# Thermistors.net
KiCad netlist of a schematic drawn in Altium Designer
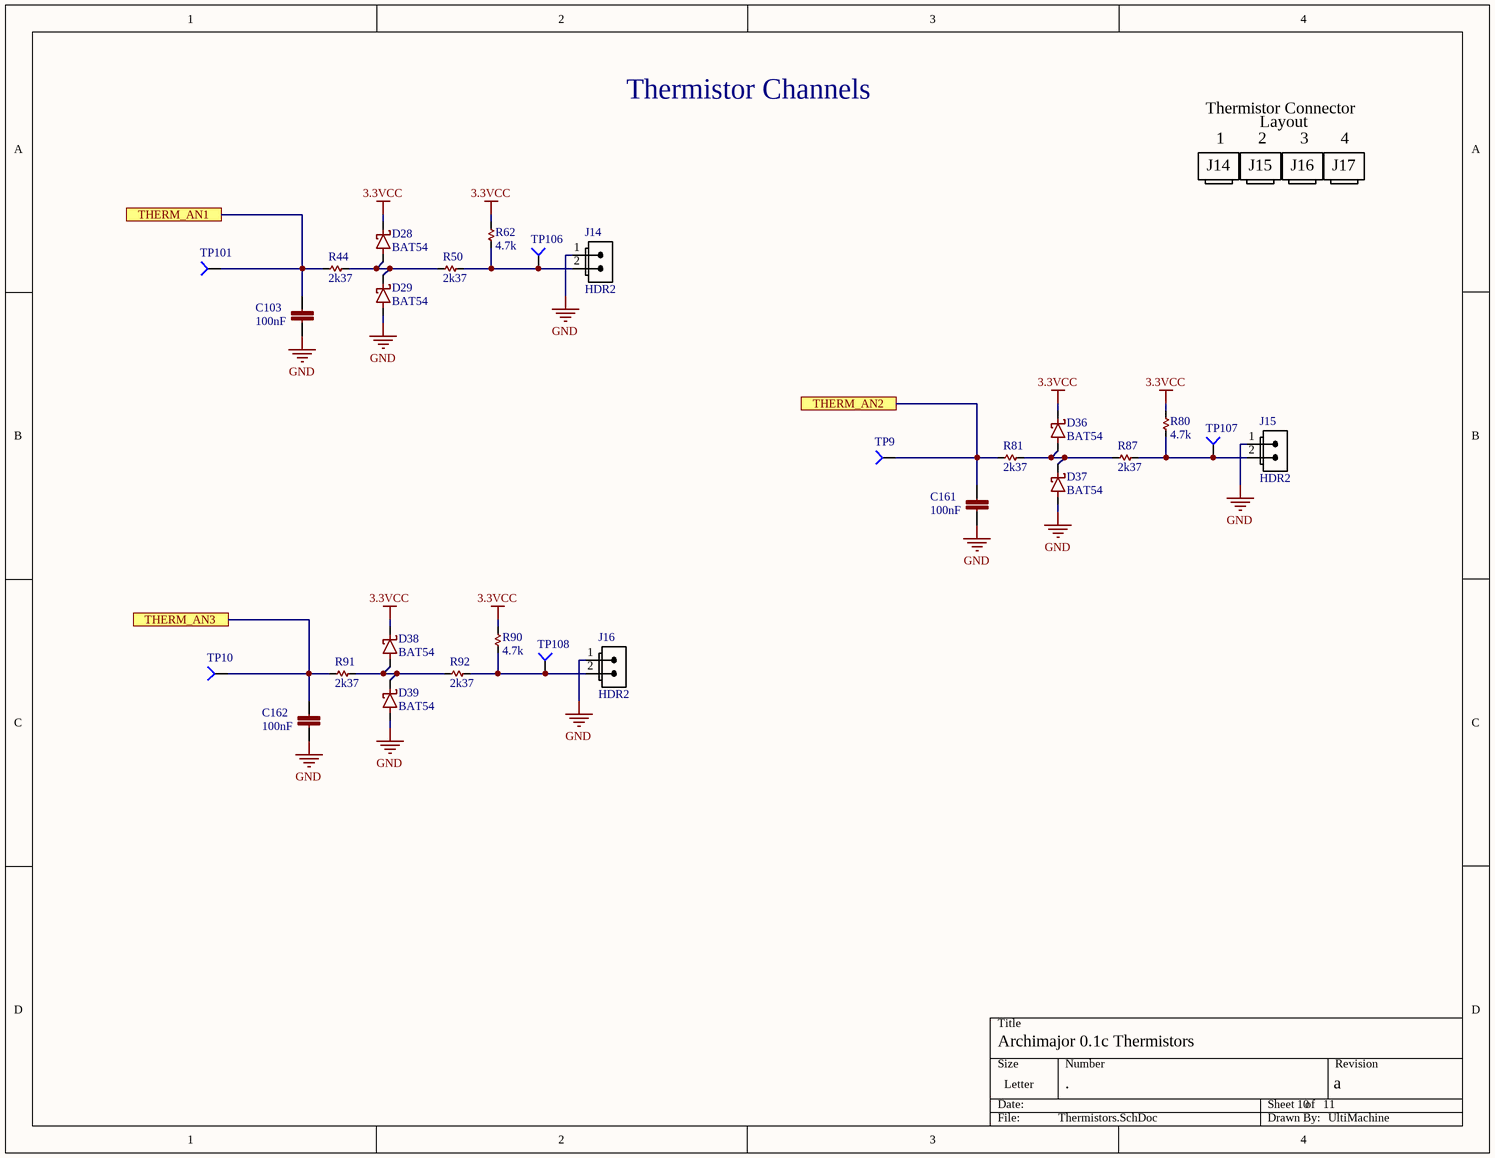
[diagram p0: Thermistors.SchDoc]

(export (version "E")
  (design (tool "Eeschema 10.0.6"))
  (components
    (comp (ref "C103")
      (value "100nF")
      (footprint "C0402")
      (description "CAP CER 0402 100nF 16V 10% X7R")
      (fields (field (name "MANUFACTURER") "Murata") (field (name "PART") "0.1uF 16V X7R 0402"))
      (libsource (lib "3Delight") (part "GRM155R71C104KA88D"))
    )
    (comp (ref "C161")
      (value "100nF")
      (footprint "C0402")
      (description "CAP CER 0402 100nF 16V 10% X7R")
      (fields (field (name "MANUFACTURER") "Murata") (field (name "PART") "0.1uF 16V X7R 0402"))
      (libsource (lib "3Delight") (part "GRM155R71C104KA88D"))
    )
    (comp (ref "C162")
      (value "100nF")
      (footprint "C0402")
      (description "CAP CER 0402 100nF 16V 10% X7R")
      (fields (field (name "MANUFACTURER") "Murata") (field (name "PART") "0.1uF 16V X7R 0402"))
      (libsource (lib "3Delight") (part "GRM155R71C104KA88D"))
    )
    (comp (ref "D28")
      (value "BAT54")
      (footprint "SOD523_IPC")
      (description "DIODE SCHOTTKY 30V 200MA SOD523")
      (fields (field (name "MANUFACTURER") "Diodes Incorporated") (field (name "PART") "Schottky Diode"))
      (libsource (lib "Diodes") (part "BAT54WX"))
    )
    (comp (ref "D29")
      (value "BAT54")
      (footprint "SOD523_IPC")
      (description "DIODE SCHOTTKY 30V 200MA SOD523")
      (fields (field (name "MANUFACTURER") "Diodes Incorporated") (field (name "PART") "Schottky Diode"))
      (libsource (lib "Diodes") (part "BAT54WX"))
    )
    (comp (ref "D36")
      (value "BAT54")
      (footprint "SOD523_IPC")
      (description "DIODE SCHOTTKY 30V 200MA SOD523")
      (fields (field (name "MANUFACTURER") "Diodes Incorporated") (field (name "PART") "Schottky Diode"))
      (libsource (lib "Diodes") (part "BAT54WX"))
    )
    (comp (ref "D37")
      (value "BAT54")
      (footprint "SOD523_IPC")
      (description "DIODE SCHOTTKY 30V 200MA SOD523")
      (fields (field (name "MANUFACTURER") "Diodes Incorporated") (field (name "PART") "Schottky Diode"))
      (libsource (lib "Diodes") (part "BAT54WX"))
    )
    (comp (ref "D38")
      (value "BAT54")
      (footprint "SOD523_IPC")
      (description "DIODE SCHOTTKY 30V 200MA SOD523")
      (fields (field (name "MANUFACTURER") "Diodes Incorporated") (field (name "PART") "Schottky Diode"))
      (libsource (lib "Diodes") (part "BAT54WX"))
    )
    (comp (ref "D39")
      (value "BAT54")
      (footprint "SOD523_IPC")
      (description "DIODE SCHOTTKY 30V 200MA SOD523")
      (fields (field (name "MANUFACTURER") "Diodes Incorporated") (field (name "PART") "Schottky Diode"))
      (libsource (lib "Diodes") (part "BAT54WX"))
    )
    (comp (ref "J14")
      (value "HDR2")
      (footprint "70543-01 PIN-IN-PASTE")
      (description "Connector 2pos - Pin in Paste")
      (fields (field (name "MANUFACTURER") "Molex") (field (name "PART") "2 Pin Conn"))
      (libsource (lib "Connectors") (part "CONN 2PIN VERT 0.1{dblquote} SHRD LOCKING PIP"))
    )
    (comp (ref "J15")
      (value "HDR2")
      (footprint "70543-01 PIN-IN-PASTE")
      (description "Connector 2pos - Pin in Paste")
      (fields (field (name "MANUFACTURER") "Molex") (field (name "PART") "2 Pin Conn"))
      (libsource (lib "Connectors") (part "CONN 2PIN VERT 0.1{dblquote} SHRD LOCKING PIP"))
    )
    (comp (ref "J16")
      (value "HDR2")
      (footprint "70543-01 PIN-IN-PASTE")
      (description "Connector 2pos - Pin in Paste")
      (fields (field (name "MANUFACTURER") "Molex") (field (name "PART") "2 Pin Conn"))
      (libsource (lib "Connectors") (part "CONN 2PIN VERT 0.1{dblquote} SHRD LOCKING PIP"))
    )
    (comp (ref "R44")
      (value "2k37")
      (footprint "R0402")
      (description "RES SMD 2.37K OHM 1% 1/16W 0402")
      (fields (field (name "MANUFACTURER") "Yageo") (field (name "PART") "2.37k 1% 0402"))
      (libsource (lib "3Delight") (part "RC0402FR-072K37L"))
    )
    (comp (ref "R50")
      (value "2k37")
      (footprint "R0402")
      (description "RES SMD 2.37K OHM 1% 1/16W 0402")
      (fields (field (name "MANUFACTURER") "Yageo") (field (name "PART") "2.37k 1% 0402"))
      (libsource (lib "3Delight") (part "RC0402FR-072K37L"))
    )
    (comp (ref "R62")
      (value "4.7k")
      (footprint "R0402")
      (description "RES SMD 4.7K OHM 1% 1/16W 0402")
      (fields (field (name "MANUFACTURER") "YAGEO") (field (name "PART") "4.7k 1% 0402"))
      (libsource (lib "3Delight") (part "RC0402FR-074K7L"))
    )
    (comp (ref "R80")
      (value "4.7k")
      (footprint "R0402")
      (description "RES SMD 4.7K OHM 1% 1/16W 0402")
      (fields (field (name "MANUFACTURER") "YAGEO") (field (name "PART") "4.7k 1% 0402"))
      (libsource (lib "3Delight") (part "RC0402FR-074K7L"))
    )
    (comp (ref "R81")
      (value "2k37")
      (footprint "R0402")
      (description "RES SMD 2.37K OHM 1% 1/16W 0402")
      (fields (field (name "MANUFACTURER") "Yageo") (field (name "PART") "2.37k 1% 0402"))
      (libsource (lib "3Delight") (part "RC0402FR-072K37L"))
    )
    (comp (ref "R87")
      (value "2k37")
      (footprint "R0402")
      (description "RES SMD 2.37K OHM 1% 1/16W 0402")
      (fields (field (name "MANUFACTURER") "Yageo") (field (name "PART") "2.37k 1% 0402"))
      (libsource (lib "3Delight") (part "RC0402FR-072K37L"))
    )
    (comp (ref "R90")
      (value "4.7k")
      (footprint "R0402")
      (description "RES SMD 4.7K OHM 1% 1/16W 0402")
      (fields (field (name "MANUFACTURER") "YAGEO") (field (name "PART") "4.7k 1% 0402"))
      (libsource (lib "3Delight") (part "RC0402FR-074K7L"))
    )
    (comp (ref "R91")
      (value "2k37")
      (footprint "R0402")
      (description "RES SMD 2.37K OHM 1% 1/16W 0402")
      (fields (field (name "MANUFACTURER") "Yageo") (field (name "PART") "2.37k 1% 0402"))
      (libsource (lib "3Delight") (part "RC0402FR-072K37L"))
    )
    (comp (ref "R92")
      (value "2k37")
      (footprint "R0402")
      (description "RES SMD 2.37K OHM 1% 1/16W 0402")
      (fields (field (name "MANUFACTURER") "Yageo") (field (name "PART") "2.37k 1% 0402"))
      (libsource (lib "3Delight") (part "RC0402FR-072K37L"))
    )
    (comp (ref "TP9")
      (value "TP4")
      (footprint "TP-2")
      (description "Socket")
      (libsource (lib "Archim") (part "Socket"))
    )
    (comp (ref "TP10")
      (value "TP4")
      (footprint "TP-2")
      (description "Socket")
      (libsource (lib "Archim") (part "Socket"))
    )
    (comp (ref "TP101")
      (value "TP4")
      (footprint "TP-2")
      (description "Socket")
      (libsource (lib "Archim") (part "Socket"))
    )
    (comp (ref "TP106")
      (value "TP4")
      (footprint "TP-2")
      (description "Socket")
      (libsource (lib "Archim") (part "Socket"))
    )
    (comp (ref "TP107")
      (value "TP4")
      (footprint "TP-2")
      (description "Socket")
      (libsource (lib "Archim") (part "Socket"))
    )
    (comp (ref "TP108")
      (value "TP4")
      (footprint "TP-2")
      (description "Socket")
      (libsource (lib "Archim") (part "Socket"))
    )
  )
  (nets
    (net (code "1") (name "/THERM_AN1") (class "Default")
      (node (ref "C103") (pin "1") (pinfunction "1_1") (pintype "passive"))
      (node (ref "R44") (pin "1") (pinfunction "1_1") (pintype "passive"))
      (node (ref "TP101") (pin "1") (pinfunction "1_1") (pintype "passive"))
    )
    (net (code "2") (name "/THERM_AN2") (class "Default")
      (node (ref "C161") (pin "1") (pinfunction "1_1") (pintype "passive"))
      (node (ref "R81") (pin "1") (pinfunction "1_1") (pintype "passive"))
      (node (ref "TP9") (pin "1") (pinfunction "1_1") (pintype "passive"))
    )
    (net (code "3") (name "/THERM_AN3") (class "Default")
      (node (ref "C162") (pin "1") (pinfunction "1_1") (pintype "passive"))
      (node (ref "R91") (pin "1") (pinfunction "1_1") (pintype "passive"))
      (node (ref "TP10") (pin "1") (pinfunction "1_1") (pintype "passive"))
    )
    (net (code "4") (name "3.3VCC") (class "Default")
      (node (ref "D28") (pin "K") (pinfunction "K_K") (pintype "passive"))
      (node (ref "D36") (pin "K") (pinfunction "K_K") (pintype "passive"))
      (node (ref "D38") (pin "K") (pinfunction "K_K") (pintype "passive"))
      (node (ref "R62") (pin "2") (pinfunction "2_2") (pintype "passive"))
      (node (ref "R80") (pin "2") (pinfunction "2_2") (pintype "passive"))
      (node (ref "R90") (pin "2") (pinfunction "2_2") (pintype "passive"))
    )
    (net (code "5") (name "GND") (class "Default")
      (node (ref "C103") (pin "2") (pinfunction "2_2") (pintype "passive"))
      (node (ref "C161") (pin "2") (pinfunction "2_2") (pintype "passive"))
      (node (ref "C162") (pin "2") (pinfunction "2_2") (pintype "passive"))
      (node (ref "D29") (pin "A") (pinfunction "A_A") (pintype "passive"))
      (node (ref "D37") (pin "A") (pinfunction "A_A") (pintype "passive"))
      (node (ref "D39") (pin "A") (pinfunction "A_A") (pintype "passive"))
      (node (ref "J14") (pin "1") (pinfunction "S_1") (pintype "passive"))
      (node (ref "J15") (pin "1") (pinfunction "S_1") (pintype "passive"))
      (node (ref "J16") (pin "1") (pinfunction "S_1") (pintype "passive"))
    )
    (net (code "6") (name "Net-(D28-PadA)") (class "Default")
      (node (ref "D28") (pin "A") (pinfunction "A_A") (pintype "passive"))
      (node (ref "D29") (pin "K") (pinfunction "K_K") (pintype "passive"))
      (node (ref "R44") (pin "2") (pinfunction "2_2") (pintype "passive"))
      (node (ref "R50") (pin "1") (pinfunction "1_1") (pintype "passive"))
    )
    (net (code "7") (name "Net-(D36-PadA)") (class "Default")
      (node (ref "D36") (pin "A") (pinfunction "A_A") (pintype "passive"))
      (node (ref "D37") (pin "K") (pinfunction "K_K") (pintype "passive"))
      (node (ref "R81") (pin "2") (pinfunction "2_2") (pintype "passive"))
      (node (ref "R87") (pin "1") (pinfunction "1_1") (pintype "passive"))
    )
    (net (code "8") (name "Net-(D38-PadA)") (class "Default")
      (node (ref "D38") (pin "A") (pinfunction "A_A") (pintype "passive"))
      (node (ref "D39") (pin "K") (pinfunction "K_K") (pintype "passive"))
      (node (ref "R91") (pin "2") (pinfunction "2_2") (pintype "passive"))
      (node (ref "R92") (pin "1") (pinfunction "1_1") (pintype "passive"))
    )
    (net (code "9") (name "Net-(J14-S-Pad2)") (class "Default")
      (node (ref "J14") (pin "2") (pinfunction "S_2") (pintype "passive"))
      (node (ref "R50") (pin "2") (pinfunction "2_2") (pintype "passive"))
      (node (ref "R62") (pin "1") (pinfunction "1_1") (pintype "passive"))
      (node (ref "TP106") (pin "1") (pinfunction "1_1") (pintype "passive"))
    )
    (net (code "10") (name "Net-(J15-S-Pad2)") (class "Default")
      (node (ref "J15") (pin "2") (pinfunction "S_2") (pintype "passive"))
      (node (ref "R80") (pin "1") (pinfunction "1_1") (pintype "passive"))
      (node (ref "R87") (pin "2") (pinfunction "2_2") (pintype "passive"))
      (node (ref "TP107") (pin "1") (pinfunction "1_1") (pintype "passive"))
    )
    (net (code "11") (name "Net-(J16-S-Pad2)") (class "Default")
      (node (ref "J16") (pin "2") (pinfunction "S_2") (pintype "passive"))
      (node (ref "R90") (pin "1") (pinfunction "1_1") (pintype "passive"))
      (node (ref "R92") (pin "2") (pinfunction "2_2") (pintype "passive"))
      (node (ref "TP108") (pin "1") (pinfunction "1_1") (pintype "passive"))
    )
  )
)
